# POWER.net
KiCad netlist of a schematic drawn in Altium Designer
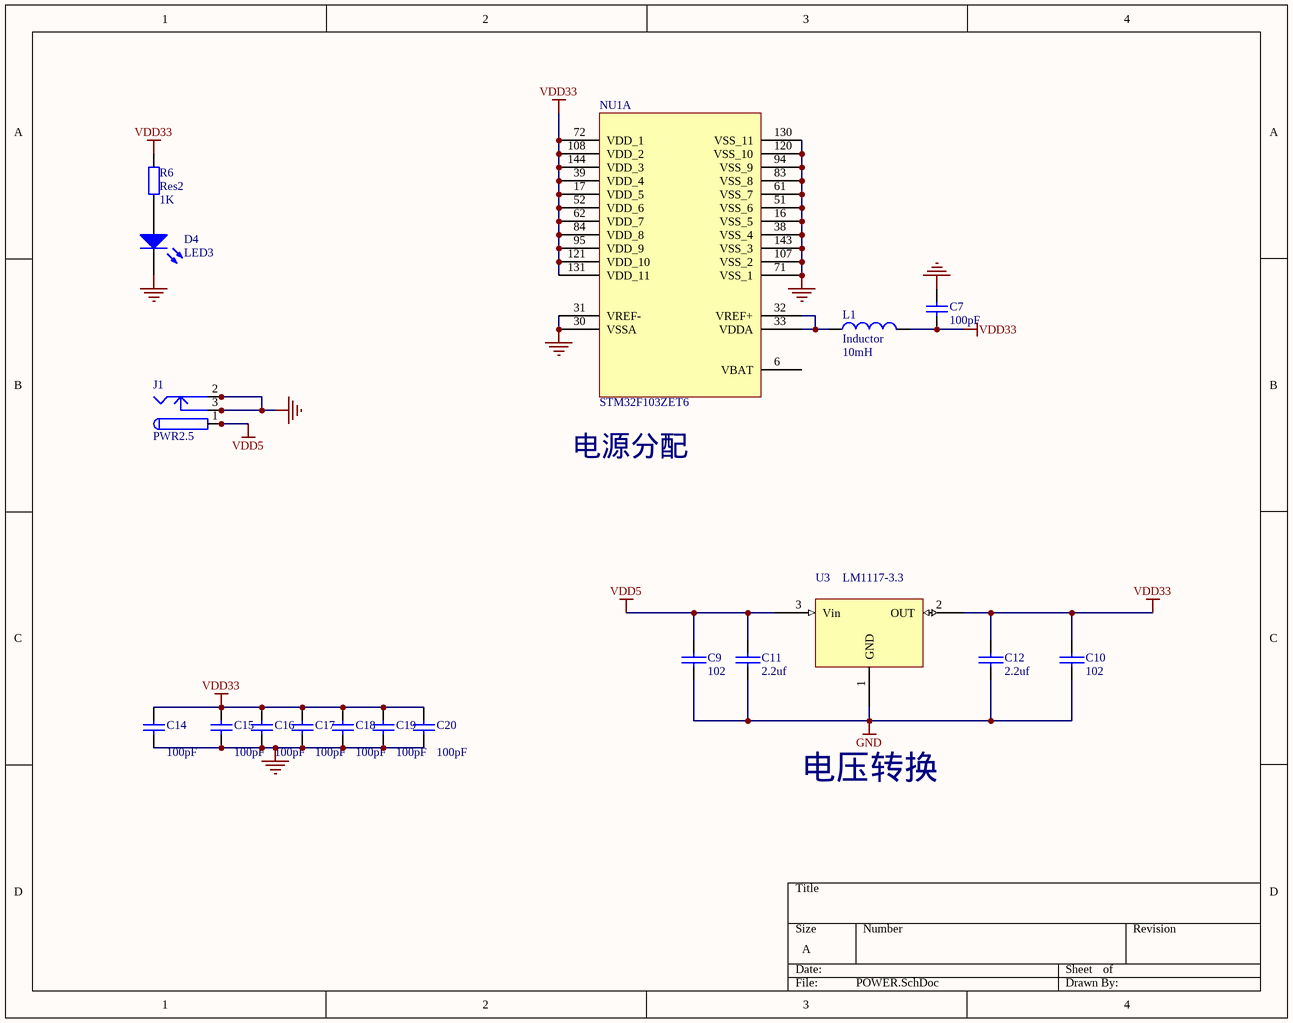
[diagram p0: POWER.SchDoc]

(export (version "E")
  (design (tool "Eeschema 10.0.6"))
  (components
    (comp (ref "C7")
      (value "100pF")
      (footprint "6-0805")
      (description "Capacitor")
      (fields (field (name "Comment") "Cap") (field (name "PUBLISHER") "Altium Limited"))
      (libsource (lib "Miscellaneous Devices") (part "Cap"))
    )
    (comp (ref "C9")
      (value "102")
      (footprint "0805")
      (description "Capacitor")
      (libsource (lib "*") (part "CAP"))
    )
    (comp (ref "C10")
      (value "102")
      (footprint "0805")
      (description "Capacitor")
      (libsource (lib "*") (part "CAP"))
    )
    (comp (ref "C11")
      (value "2.2uf")
      (footprint "1210")
      (description "Capacitor")
      (libsource (lib "*") (part "CAP"))
    )
    (comp (ref "C12")
      (value "2.2uf")
      (footprint "1210")
      (description "Capacitor")
      (libsource (lib "*") (part "CAP"))
    )
    (comp (ref "C14")
      (value "100pF")
      (footprint "6-0805")
      (description "Capacitor")
      (fields (field (name "Comment") "Cap") (field (name "PUBLISHER") "Altium Limited"))
      (libsource (lib "Miscellaneous Devices") (part "Cap"))
    )
    (comp (ref "C15")
      (value "100pF")
      (footprint "6-0805")
      (description "Capacitor")
      (fields (field (name "Comment") "Cap") (field (name "PUBLISHER") "Altium Limited"))
      (libsource (lib "Miscellaneous Devices") (part "Cap"))
    )
    (comp (ref "C16")
      (value "100pF")
      (footprint "6-0805")
      (description "Capacitor")
      (fields (field (name "Comment") "Cap") (field (name "PUBLISHER") "Altium Limited"))
      (libsource (lib "Miscellaneous Devices") (part "Cap"))
    )
    (comp (ref "C17")
      (value "100pF")
      (footprint "6-0805")
      (description "Capacitor")
      (fields (field (name "Comment") "Cap") (field (name "PUBLISHER") "Altium Limited"))
      (libsource (lib "Miscellaneous Devices") (part "Cap"))
    )
    (comp (ref "C18")
      (value "100pF")
      (footprint "6-0805")
      (description "Capacitor")
      (fields (field (name "Comment") "Cap") (field (name "PUBLISHER") "Altium Limited"))
      (libsource (lib "Miscellaneous Devices") (part "Cap"))
    )
    (comp (ref "C19")
      (value "100pF")
      (footprint "6-0805")
      (description "Capacitor")
      (fields (field (name "Comment") "Cap") (field (name "PUBLISHER") "Altium Limited"))
      (libsource (lib "Miscellaneous Devices") (part "Cap"))
    )
    (comp (ref "C20")
      (value "100pF")
      (footprint "6-0805")
      (description "Capacitor")
      (fields (field (name "Comment") "Cap") (field (name "PUBLISHER") "Altium Limited"))
      (libsource (lib "Miscellaneous Devices") (part "Cap"))
    )
    (comp (ref "D4")
      (value "LED3")
      (footprint "0805")
      (description "Typical BLUE SiC LED")
      (fields (field (name "PUBLISHER") "Altium Limited"))
      (libsource (lib "Miscellaneous Devices") (part "LED3"))
    )
    (comp (ref "J1")
      (value "PWR2.5")
      (footprint "Power_In")
      (description "Low Voltage Power Supply Connector")
      (fields (field (name "PUBLISHER") "Altium Limited"))
      (libsource (lib "Miscellaneous Connectors") (part "PWR2.5"))
    )
    (comp (ref "L1")
      (value "Inductor")
      (footprint "6-0805")
      (fields (field (name "ALTIUM_VALUE") "10mH") (field (name "PUBLISHER") "Altium Limited"))
      (libsource (lib "Miscellaneous Devices") (part "Inductor"))
    )
    (comp (ref "NU1")
      (value "STM32F103ZET6")
      (footprint "LQFN144")
      (libsource (lib "Schlib1") (part "STM32F103ZET6"))
    )
    (comp (ref "R6")
      (value "Res2")
      (footprint "0805")
      (description "Resistor")
      (fields (field (name "ALTIUM_VALUE") "1K") (field (name "PUBLISHER") "Altium Limited"))
      (libsource (lib "Miscellaneous Devices") (part "Res2"))
    )
    (comp (ref "U3") (value "LM1117-3.3") (footprint "SOT-223") (libsource (lib "*") (part "LM1117-3.3")))
  )
  (nets
    (net (code "1") (name "GND") (class "Default")
      (node (ref "C10") (pin "2") (pinfunction "2_2") (pintype "passive"))
      (node (ref "C11") (pin "2") (pinfunction "2_2") (pintype "passive"))
      (node (ref "C12") (pin "2") (pinfunction "2_2") (pintype "passive"))
      (node (ref "C14") (pin "1") (pinfunction "1_1") (pintype "passive"))
      (node (ref "C15") (pin "1") (pinfunction "1_1") (pintype "passive"))
      (node (ref "C16") (pin "1") (pinfunction "1_1") (pintype "passive"))
      (node (ref "C17") (pin "1") (pinfunction "1_1") (pintype "passive"))
      (node (ref "C18") (pin "1") (pinfunction "1_1") (pintype "passive"))
      (node (ref "C19") (pin "1") (pinfunction "1_1") (pintype "passive"))
      (node (ref "C20") (pin "1") (pinfunction "1_1") (pintype "passive"))
      (node (ref "C7") (pin "1") (pinfunction "1_1") (pintype "passive"))
      (node (ref "C9") (pin "2") (pinfunction "2_2") (pintype "passive"))
      (node (ref "D4") (pin "2") (pinfunction "K_2") (pintype "passive"))
      (node (ref "J1") (pin "2") (pinfunction "2_2") (pintype "power_in"))
      (node (ref "J1") (pin "2B") (pinfunction "2B_2B") (pintype "power_in"))
      (node (ref "J1") (pin "3") (pinfunction "3_3") (pintype "power_in"))
      (node (ref "J1") (pin "3B") (pinfunction "3B_3B") (pintype "power_in"))
      (node (ref "NU1") (pin "107") (pinfunction "VSS_2_107") (pintype "passive"))
      (node (ref "NU1") (pin "120") (pinfunction "VSS_10_120") (pintype "passive"))
      (node (ref "NU1") (pin "130") (pinfunction "VSS_11_130") (pintype "passive"))
      (node (ref "NU1") (pin "143") (pinfunction "VSS_3_143") (pintype "passive"))
      (node (ref "NU1") (pin "16") (pinfunction "VSS_5_16") (pintype "passive"))
      (node (ref "NU1") (pin "30") (pinfunction "VSSA_30") (pintype "passive"))
      (node (ref "NU1") (pin "31") (pinfunction "VREF-_31") (pintype "passive"))
      (node (ref "NU1") (pin "38") (pinfunction "VSS_4_38") (pintype "passive"))
      (node (ref "NU1") (pin "51") (pinfunction "VSS_6_51") (pintype "passive"))
      (node (ref "NU1") (pin "61") (pinfunction "VSS_7_61") (pintype "passive"))
      (node (ref "NU1") (pin "71") (pinfunction "VSS_1_71") (pintype "passive"))
      (node (ref "NU1") (pin "83") (pinfunction "VSS_8_83") (pintype "passive"))
      (node (ref "NU1") (pin "94") (pinfunction "VSS_9_94") (pintype "passive"))
      (node (ref "U3") (pin "1") (pinfunction "GND_1") (pintype "power_in"))
    )
    (net (code "2") (name "Net-(D4-A)") (class "Default")
      (node (ref "D4") (pin "1") (pinfunction "A_1") (pintype "passive"))
      (node (ref "R6") (pin "1") (pinfunction "1_1") (pintype "passive"))
    )
    (net (code "3") (name "Net-(NU1A-VDDA)") (class "Default")
      (node (ref "L1") (pin "1") (pinfunction "1_1") (pintype "passive"))
      (node (ref "NU1") (pin "32") (pinfunction "VREF+_32") (pintype "passive"))
      (node (ref "NU1") (pin "33") (pinfunction "VDDA_33") (pintype "passive"))
    )
    (net (code "4") (name "VDD5") (class "Default")
      (node (ref "C11") (pin "1") (pinfunction "1_1") (pintype "passive"))
      (node (ref "C9") (pin "1") (pinfunction "1_1") (pintype "passive"))
      (node (ref "J1") (pin "1") (pinfunction "1_1") (pintype "power_in"))
      (node (ref "J1") (pin "1B") (pinfunction "1B_1B") (pintype "power_in"))
      (node (ref "U3") (pin "3") (pinfunction "Vin_3") (pintype "input"))
    )
    (net (code "5") (name "VDD33") (class "Default")
      (node (ref "C10") (pin "1") (pinfunction "1_1") (pintype "passive"))
      (node (ref "C12") (pin "1") (pinfunction "1_1") (pintype "passive"))
      (node (ref "C14") (pin "2") (pinfunction "2_2") (pintype "passive"))
      (node (ref "C15") (pin "2") (pinfunction "2_2") (pintype "passive"))
      (node (ref "C16") (pin "2") (pinfunction "2_2") (pintype "passive"))
      (node (ref "C17") (pin "2") (pinfunction "2_2") (pintype "passive"))
      (node (ref "C18") (pin "2") (pinfunction "2_2") (pintype "passive"))
      (node (ref "C19") (pin "2") (pinfunction "2_2") (pintype "passive"))
      (node (ref "C20") (pin "2") (pinfunction "2_2") (pintype "passive"))
      (node (ref "C7") (pin "2") (pinfunction "2_2") (pintype "passive"))
      (node (ref "L1") (pin "2") (pinfunction "2_2") (pintype "passive"))
      (node (ref "NU1") (pin "108") (pinfunction "VDD_2_108") (pintype "passive"))
      (node (ref "NU1") (pin "121") (pinfunction "VDD_10_121") (pintype "passive"))
      (node (ref "NU1") (pin "131") (pinfunction "VDD_11_131") (pintype "passive"))
      (node (ref "NU1") (pin "144") (pinfunction "VDD_3_144") (pintype "passive"))
      (node (ref "NU1") (pin "17") (pinfunction "VDD_5_17") (pintype "passive"))
      (node (ref "NU1") (pin "39") (pinfunction "VDD_4_39") (pintype "passive"))
      (node (ref "NU1") (pin "52") (pinfunction "VDD_6_52") (pintype "passive"))
      (node (ref "NU1") (pin "62") (pinfunction "VDD_7_62") (pintype "passive"))
      (node (ref "NU1") (pin "72") (pinfunction "VDD_1_72") (pintype "passive"))
      (node (ref "NU1") (pin "84") (pinfunction "VDD_8_84") (pintype "passive"))
      (node (ref "NU1") (pin "95") (pinfunction "VDD_9_95") (pintype "passive"))
      (node (ref "R6") (pin "2") (pinfunction "2_2") (pintype "passive"))
      (node (ref "U3") (pin "2") (pinfunction "OUT_2") (pintype "bidirectional"))
    )
    (net (code "6") (name "unconnected-(NU1A-VBAT-Pad6)") (class "Default")
      (node (ref "NU1") (pin "6") (pinfunction "VBAT_6") (pintype "passive"))
    )
  )
)
